# gps-breakout-mk-1_4_1.net
KiCad netlist of a schematic drawn in EAGLE
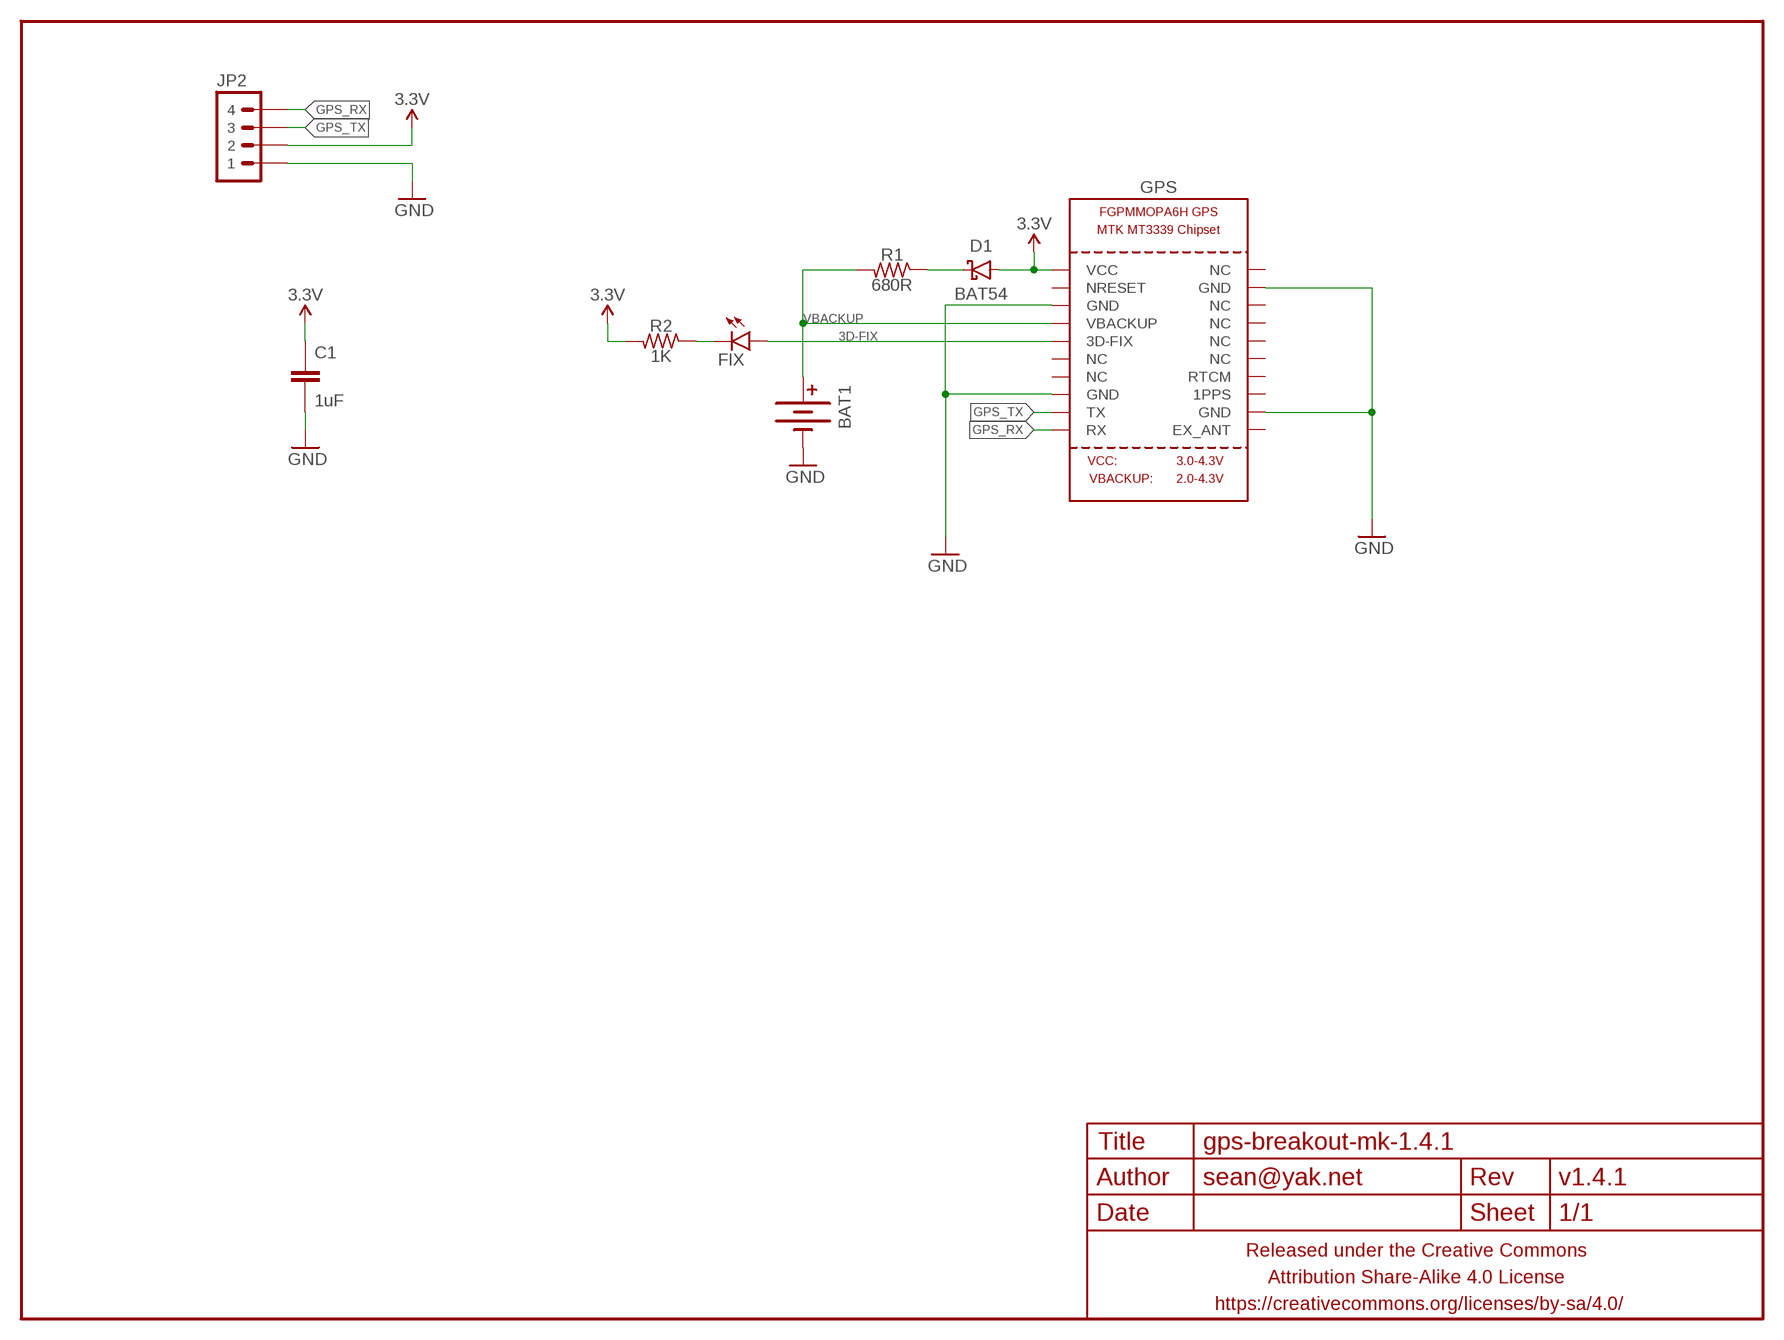
[diagram p0: schematic, sheet 1]

(export (version "E")
  (design (tool "Eeschema 10.0.6"))
  (components
    (comp (ref "BAT1")
      (value "BATTERYML414")
      (footprint "eagle-import:BATTCON_4.8MM")
      (libsource (lib "eagle-import") (part "BATTERYML414"))
    )
    (comp (ref "C1")
      (value "1uF")
      (footprint "eagle-import:C0603-TIGHTER")
      (libsource (lib "eagle-import") (part "CAPACITOR-CERAMICC0603-TIGHTER"))
    )
    (comp (ref "D1")
      (value "BAT54")
      (footprint "eagle-import:SOD323-SCHOTTKY")
      (libsource (lib "eagle-import") (part "DIODE-SCHOTTKYSOD323"))
    )
    (comp (ref "FIX")
      (value "LED0603-TIGHT")
      (footprint "eagle-import:LED-0603-TIGHT")
      (libsource (lib "eagle-import") (part "LED0603-TIGHT"))
    )
    (comp (ref "FRAME1")
      (value "FRAME-LETTERNO_PACKAGE")
      (footprint "eagle-import:DUMMY")
      (fields
        (field (name "DESIGNER") "Nobody")
        (field (name "VERSION") "v01")
        (field (name "DESIGNER_1") "sean@yak.net")
        (field (name "VERSION_1") "v1.4.1")
      )
      (libsource (lib "eagle-import") (part "FRAME-LETTERNO_PACKAGE"))
    )
    (comp (ref "GPS")
      (value "GPS_FGPMMOPA6H")
      (footprint "eagle-import:FGPMMOPA6H")
      (libsource (lib "eagle-import") (part "GPS_FGPMMOPA6H"))
    )
    (comp (ref "JP2")
      (value "M04SMD-FEMALE-DUAL")
      (footprint "eagle-import:1X04-SMD-FEMALE-RA-DUAL")
      (libsource (lib "eagle-import") (part "M04SMD-FEMALE-DUAL"))
    )
    (comp (ref "R1")
      (value "680R")
      (footprint "eagle-import:R0603-TIGHTER")
      (libsource (lib "eagle-import") (part "RESISTORR0603-TIGHTER"))
    )
    (comp (ref "R2")
      (value "1K")
      (footprint "eagle-import:R0603-TIGHTER")
      (libsource (lib "eagle-import") (part "RESISTORR0603-TIGHTER"))
    )
  )
  (nets
    (net (code "1") (name "/3D-FIX") (class "Default")
      (node (ref "FIX") (pin "A") (pinfunction "A_A") (pintype "passive"))
      (node (ref "GPS") (pin "P$5") (pinfunction "3D-FIX_P$5") (pintype "bidirectional"))
    )
    (net (code "2") (name "/VBACKUP") (class "Default")
      (node (ref "BAT1") (pin "A1") (pinfunction "+_A1") (pintype "power_in"))
      (node (ref "BAT1") (pin "A2") (pinfunction "+_A2") (pintype "power_in"))
      (node (ref "GPS") (pin "P$4") (pinfunction "VBACKUP_P$4") (pintype "bidirectional"))
      (node (ref "R1") (pin "2") (pinfunction "2_2") (pintype "passive"))
    )
    (net (code "3") (name "3.3V") (class "Default")
      (node (ref "C1") (pin "1") (pinfunction "1_1") (pintype "passive"))
      (node (ref "D1") (pin "A") (pinfunction "A_A") (pintype "passive"))
      (node (ref "GPS") (pin "P$1") (pinfunction "VCC_P$1") (pintype "bidirectional"))
      (node (ref "JP2") (pin "P$2") (pinfunction "2_P$2") (pintype "passive"))
      (node (ref "JP2") (pin "P$2_1") (pinfunction "2_P$2_1") (pintype "passive"))
      (node (ref "R2") (pin "2") (pinfunction "2_2") (pintype "passive"))
    )
    (net (code "4") (name "GND") (class "Default")
      (node (ref "BAT1") (pin "-") (pinfunction "-_-") (pintype "power_in"))
      (node (ref "C1") (pin "2") (pinfunction "2_2") (pintype "passive"))
      (node (ref "GPS") (pin "P$12") (pinfunction "GND_P$12") (pintype "bidirectional"))
      (node (ref "GPS") (pin "P$19") (pinfunction "GND_P$19") (pintype "bidirectional"))
      (node (ref "GPS") (pin "P$3") (pinfunction "GND_P$3") (pintype "bidirectional"))
      (node (ref "GPS") (pin "P$8") (pinfunction "GND_P$8") (pintype "bidirectional"))
      (node (ref "JP2") (pin "P$1") (pinfunction "1_P$1") (pintype "passive"))
      (node (ref "JP2") (pin "P$1_1") (pinfunction "1_P$1_1") (pintype "passive"))
    )
    (net (code "5") (name "GPS_RX") (class "Default")
      (node (ref "GPS") (pin "P$10") (pinfunction "RX_P$10") (pintype "bidirectional"))
      (node (ref "JP2") (pin "P$4") (pinfunction "4_P$4") (pintype "passive"))
      (node (ref "JP2") (pin "P$4_1") (pinfunction "4_P$4_1") (pintype "passive"))
    )
    (net (code "6") (name "GPS_TX") (class "Default")
      (node (ref "GPS") (pin "P$9") (pinfunction "TX_P$9") (pintype "bidirectional"))
      (node (ref "JP2") (pin "P$3") (pinfunction "3_P$3") (pintype "passive"))
      (node (ref "JP2") (pin "P$3_1") (pinfunction "3_P$3_1") (pintype "passive"))
    )
    (net (code "7") (name "Net-(D1-PadC)") (class "Default")
      (node (ref "D1") (pin "C") (pinfunction "C_C") (pintype "passive"))
      (node (ref "R1") (pin "1") (pinfunction "1_1") (pintype "passive"))
    )
    (net (code "8") (name "Net-(FIX-PadC)") (class "Default")
      (node (ref "FIX") (pin "C") (pinfunction "C_C") (pintype "passive"))
      (node (ref "R2") (pin "1") (pinfunction "1_1") (pintype "passive"))
    )
    (net (code "9") (name "unconnected-(GPS-1PPS-PadP$13)") (class "Default")
      (node (ref "GPS") (pin "P$13") (pinfunction "1PPS_P$13") (pintype "bidirectional"))
    )
    (net (code "10") (name "unconnected-(GPS-EX_ANT-PadP$11)") (class "Default")
      (node (ref "GPS") (pin "P$11") (pinfunction "EX_ANT_P$11") (pintype "bidirectional"))
    )
    (net (code "11") (name "unconnected-(GPS-NC-PadP$6)") (class "Default")
      (node (ref "GPS") (pin "P$6") (pinfunction "NC_P$6") (pintype "bidirectional"))
    )
    (net (code "12") (name "unconnected-(GPS-NC-PadP$7)") (class "Default")
      (node (ref "GPS") (pin "P$7") (pinfunction "NC_P$7") (pintype "bidirectional"))
    )
    (net (code "13") (name "unconnected-(GPS-NC-PadP$15)") (class "Default")
      (node (ref "GPS") (pin "P$15") (pinfunction "NC_P$15") (pintype "bidirectional"))
    )
    (net (code "14") (name "unconnected-(GPS-NC-PadP$16)") (class "Default")
      (node (ref "GPS") (pin "P$16") (pinfunction "NC_P$16") (pintype "bidirectional"))
    )
    (net (code "15") (name "unconnected-(GPS-NC-PadP$17)") (class "Default")
      (node (ref "GPS") (pin "P$17") (pinfunction "NC_P$17") (pintype "bidirectional"))
    )
    (net (code "16") (name "unconnected-(GPS-NC-PadP$18)") (class "Default")
      (node (ref "GPS") (pin "P$18") (pinfunction "NC_P$18") (pintype "bidirectional"))
    )
    (net (code "17") (name "unconnected-(GPS-NC-PadP$20)") (class "Default")
      (node (ref "GPS") (pin "P$20") (pinfunction "NC_P$20") (pintype "bidirectional"))
    )
    (net (code "18") (name "unconnected-(GPS-NRESET-PadP$2)") (class "Default")
      (node (ref "GPS") (pin "P$2") (pinfunction "NRESET_P$2") (pintype "bidirectional"))
    )
    (net (code "19") (name "unconnected-(GPS-RTCM-PadP$14)") (class "Default")
      (node (ref "GPS") (pin "P$14") (pinfunction "RTCM_P$14") (pintype "bidirectional"))
    )
  )
)
